# SMA_RF_CLK.net
KiCad netlist of a schematic drawn in Altium Designer
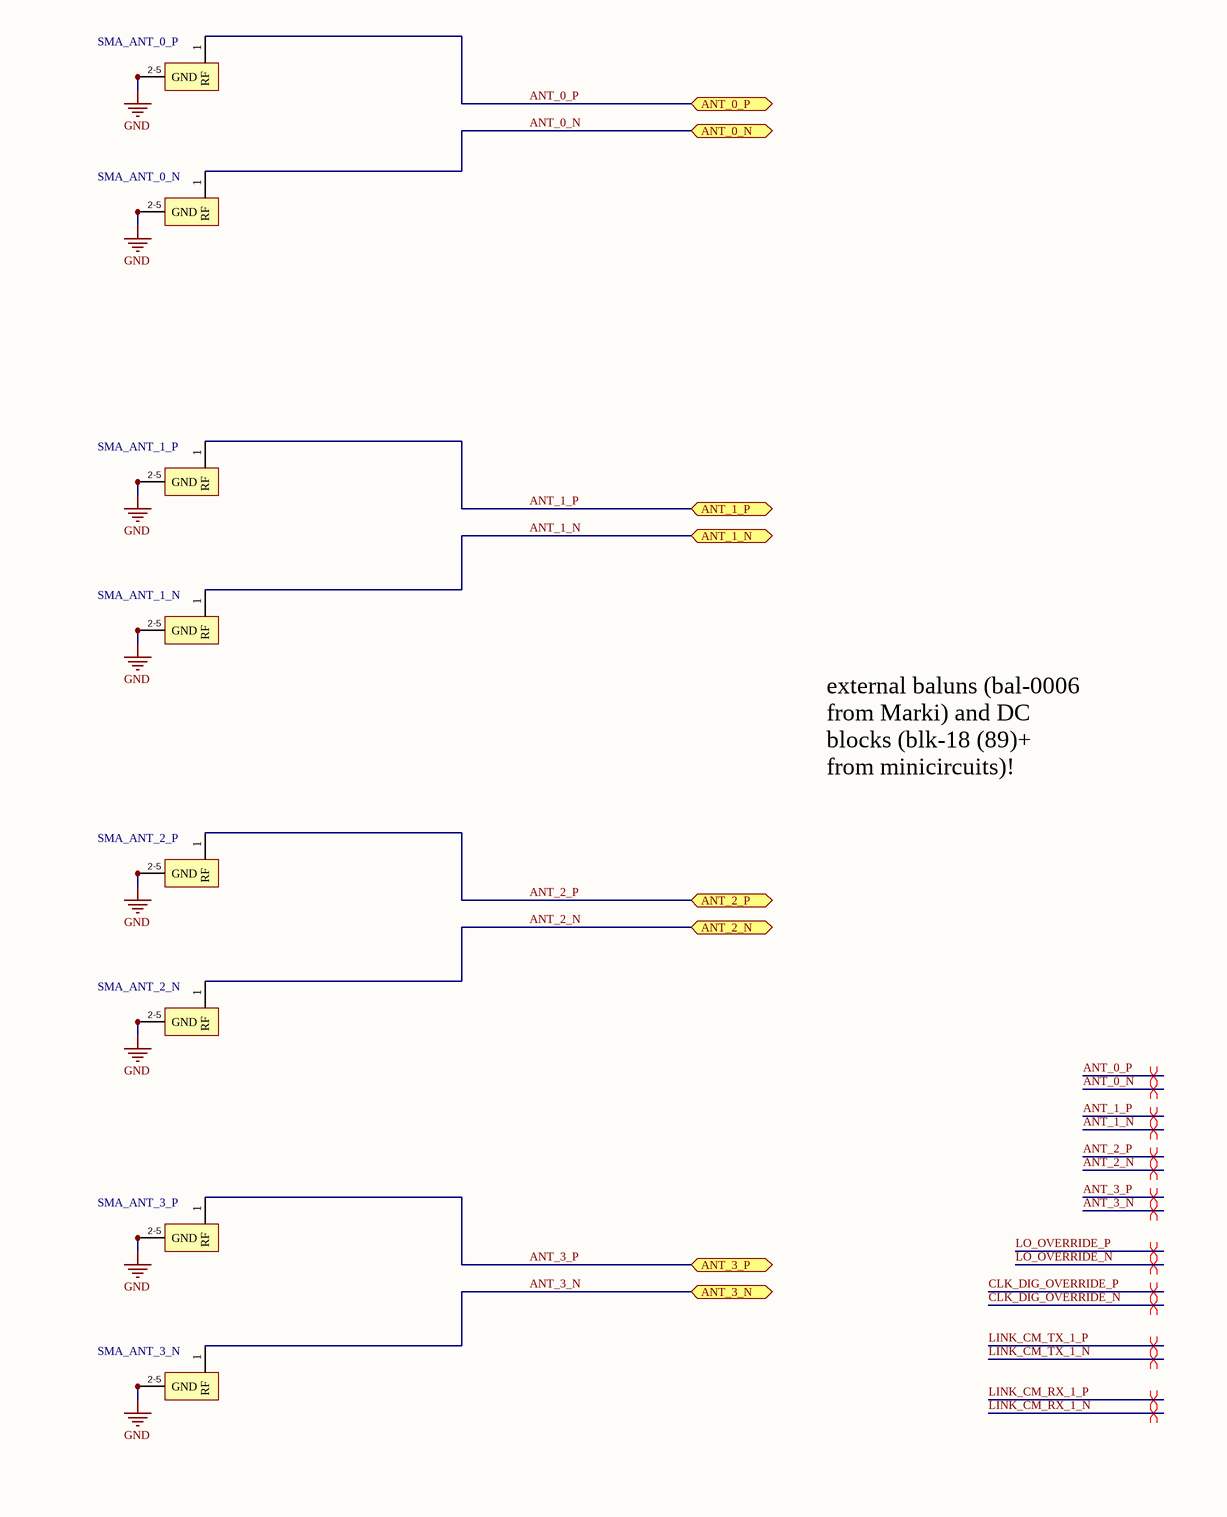
[diagram p0: SMA_RF_CLK.SchDoc, top]
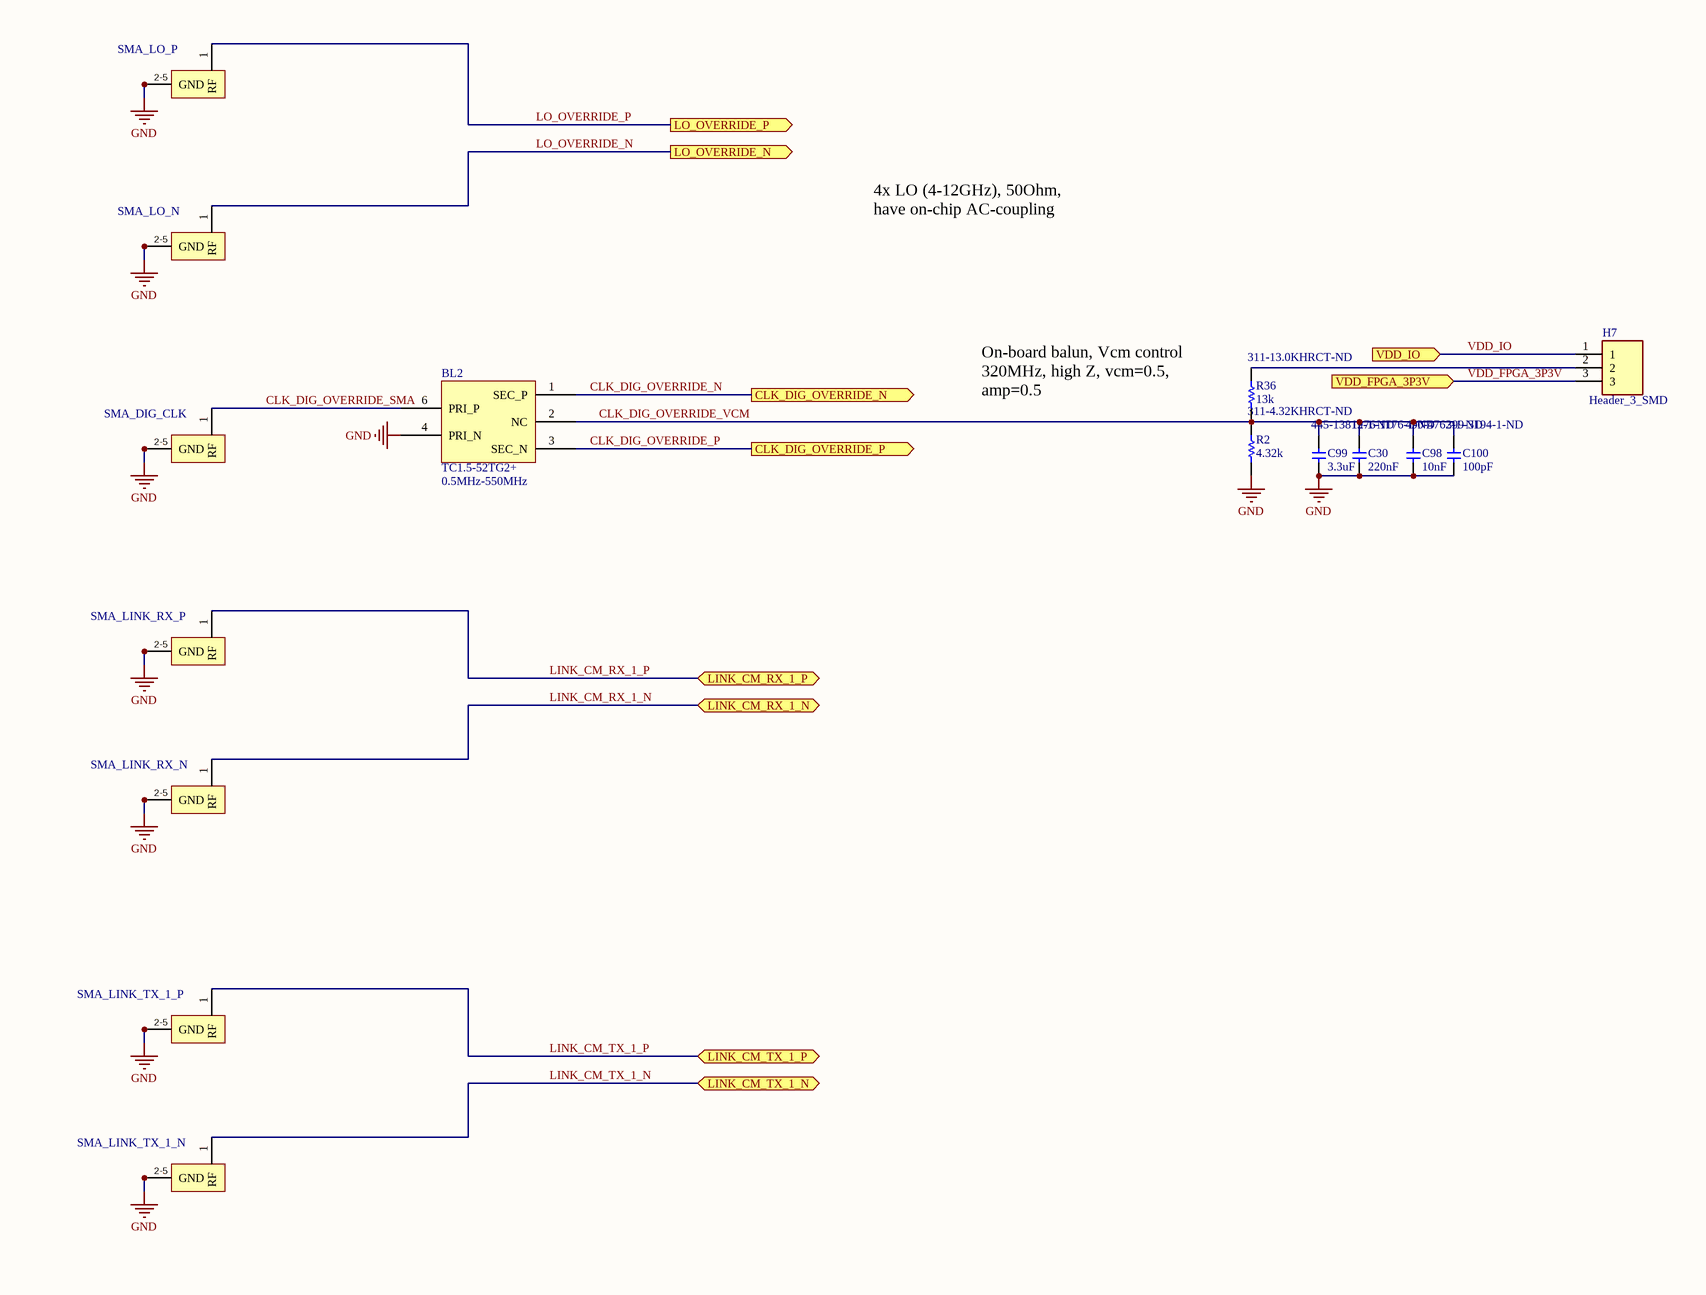
[diagram p1: SMA_RF_CLK.SchDoc, centre]
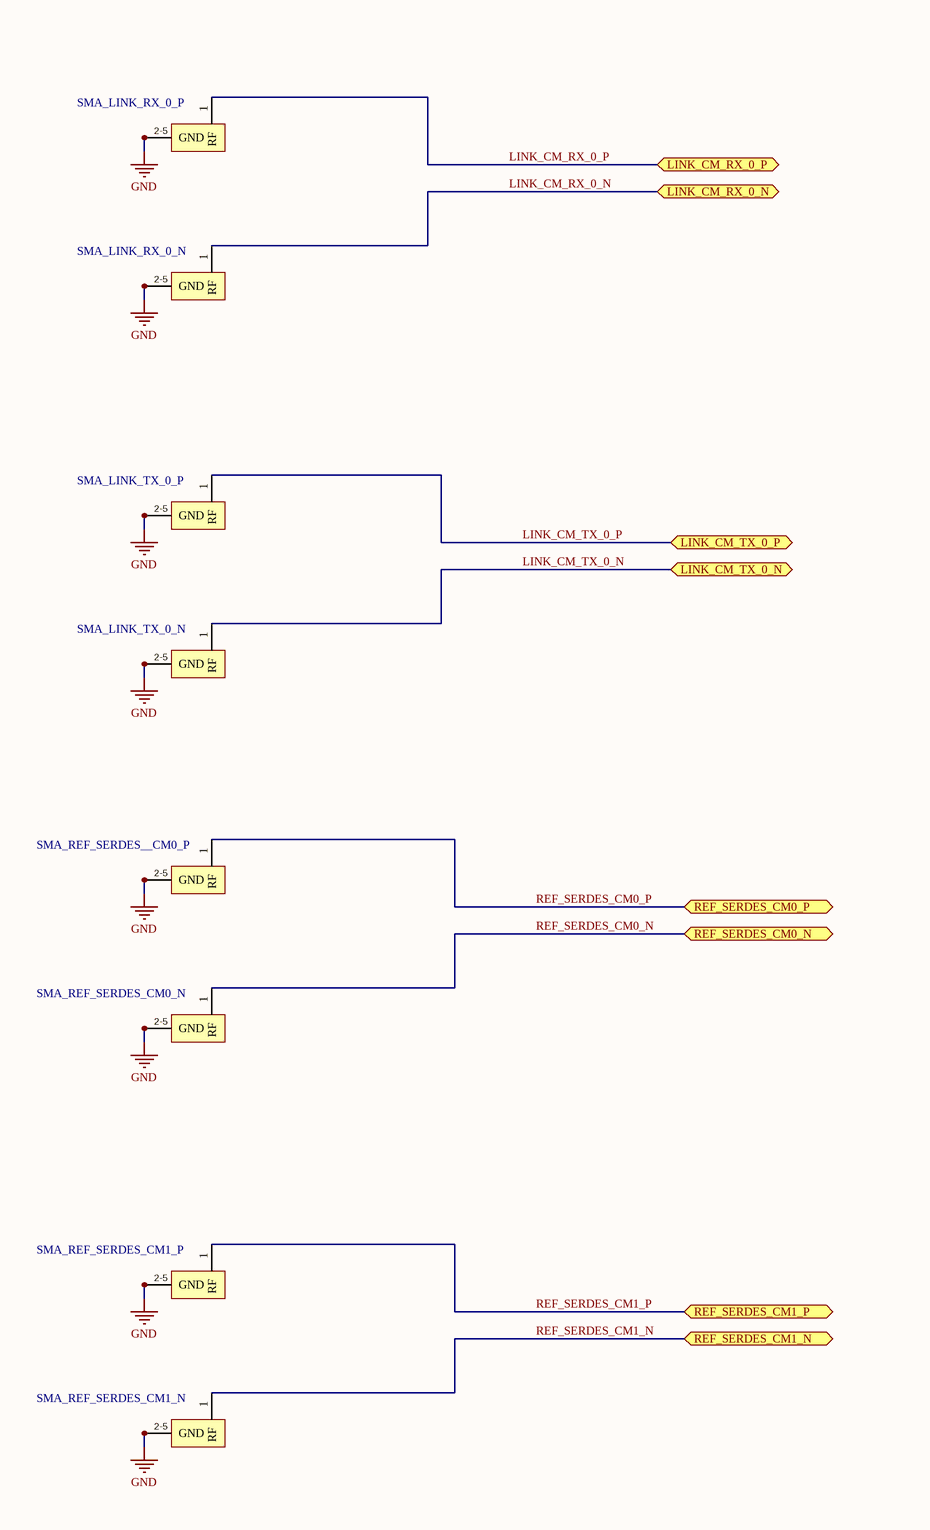
[diagram p2: SMA_RF_CLK.SchDoc, bottom]

(export (version "E")
  (design (tool "Eeschema 10.0.6"))
  (components
    (comp (ref "BL2")
      (value "TC1.5-52TG2+")
      (footprint "AT224-3")
      (description "Balun, 1:1.5 CORE & WIRE Transformer, 0.5 - 550 MHz, 50Ω")
      (fields (field (name "MANUFACTURER") "Mini-Circuits") (field (name "FREQUENCY RANGE") "0.5MHz-550MHz"))
      (libsource (lib "fader2_parts") (part "TC1.5-52TG2+"))
    )
    (comp (ref "C30")
      (value "220nF")
      (footprint "CAP_0402")
      (description "CAP CER 0.22uF 10% 16V X7R 0402")
      (fields
        (field (name "MANUFACTURER") "Samsung Electro-Mechanics")
        (field (name "SUPPLIER PART NUMBER 1") "1276-1176-1-ND")
      )
      (libsource (lib "fader2_parts") (part "cap 220nF"))
    )
    (comp (ref "C98")
      (value "10nF")
      (footprint "CAPC1005X06L_HD")
      (description "CAP CER 10nF 10% 50V X7R 0402")
      (fields (field (name "MANUFACTURER") "Murata") (field (name "SUPPLIER PART NUMBER 1") "490-4762-1-ND"))
      (libsource (lib "fader2_parts") (part "cap 10nF"))
    )
    (comp (ref "C99")
      (value "3.3uF")
      (footprint "CAP_0402")
      (description "CAP CER 3.3uF 10% 10V X5R 0402")
      (fields (field (name "MANUFACTURER") "TDK") (field (name "SUPPLIER PART NUMBER 1") "445-13819-1-ND"))
      (libsource (lib "fader2_parts") (part "cap 3p3uF"))
    )
    (comp (ref "C100")
      (value "100pF")
      (footprint "CAPC1005X06L_HD")
      (description "CAP CER 100pF 5% 50V C0G/NP0 0402")
      (fields (field (name "MANUFACTURER") "Kemet") (field (name "SUPPLIER PART NUMBER 1") "399-3194-1-ND"))
      (libsource (lib "fader2_parts") (part "cap 100pF 0402"))
    )
    (comp (ref "H7")
      (value "Header_3_SMD")
      (footprint "HDR1X3_SMD")
      (description "Connector Header Vertical, SMD, 3 position 0.100\" (2.54mm)")
      (fields
        (field (name "MANUFACTURER_PART_NUMBER") "TSM-103-01-S-SV-P-TR")
        (field (name "MOUSER PART NUMBER") "200-TSM10301SSVPTR")
      )
      (libsource (lib "fader2_parts") (part "Header_3_SMD"))
    )
    (comp (ref "R2")
      (value "4.32k")
      (footprint "RES_0603")
      (description "RES SMD 4.32kOHM 1% 1/10W 0603")
      (fields (field (name "SUPPLIER PART NUMBER 1") "311-4.32KHRCT-ND"))
      (libsource (lib "fader2_parts") (part "res 4.32 kOhm_1"))
    )
    (comp (ref "R36")
      (value "13k")
      (footprint "RES_0603")
      (description "RES SMD 13k OHM 1% 1/10W 0603")
      (fields (field (name "SUPPLIER PART NUMBER 1") "311-13.0KHRCT-ND"))
      (libsource (lib "fader2_parts") (part "res 13 kOhm_1"))
    )
    (comp (ref "SMA_ANT_0_N")
      (value "CONSMA001-SMD-G")
      (footprint "CON-SMA-SMD")
      (description "SMD SMA CONNECTOR")
      (libsource (lib "fader2_parts") (part "SURFACE MOUNT SMA CONNECTOR"))
    )
    (comp (ref "SMA_ANT_0_P")
      (value "CONSMA001-SMD-G")
      (footprint "CON-SMA-SMD")
      (description "SMD SMA CONNECTOR")
      (libsource (lib "fader2_parts") (part "SURFACE MOUNT SMA CONNECTOR"))
    )
    (comp (ref "SMA_ANT_1_N")
      (value "CONSMA001-SMD-G")
      (footprint "CON-SMA-SMD")
      (description "SMD SMA CONNECTOR")
      (libsource (lib "fader2_parts") (part "SURFACE MOUNT SMA CONNECTOR"))
    )
    (comp (ref "SMA_ANT_1_P")
      (value "CONSMA001-SMD-G")
      (footprint "CON-SMA-SMD")
      (description "SMD SMA CONNECTOR")
      (libsource (lib "fader2_parts") (part "SURFACE MOUNT SMA CONNECTOR"))
    )
    (comp (ref "SMA_ANT_2_N")
      (value "CONSMA001-SMD-G")
      (footprint "CON-SMA-SMD")
      (description "SMD SMA CONNECTOR")
      (libsource (lib "fader2_parts") (part "SURFACE MOUNT SMA CONNECTOR"))
    )
    (comp (ref "SMA_ANT_2_P")
      (value "CONSMA001-SMD-G")
      (footprint "CON-SMA-SMD")
      (description "SMD SMA CONNECTOR")
      (libsource (lib "fader2_parts") (part "SURFACE MOUNT SMA CONNECTOR"))
    )
    (comp (ref "SMA_ANT_3_N")
      (value "CONSMA001-SMD-G")
      (footprint "CON-SMA-SMD")
      (description "SMD SMA CONNECTOR")
      (libsource (lib "fader2_parts") (part "SURFACE MOUNT SMA CONNECTOR"))
    )
    (comp (ref "SMA_ANT_3_P")
      (value "CONSMA001-SMD-G")
      (footprint "CON-SMA-SMD")
      (description "SMD SMA CONNECTOR")
      (libsource (lib "fader2_parts") (part "SURFACE MOUNT SMA CONNECTOR"))
    )
    (comp (ref "SMA_DIG_CLK")
      (value "CONSMA001-SMD-G")
      (footprint "CON-SMA-SMD")
      (description "SMD SMA CONNECTOR")
      (libsource (lib "fader2_parts") (part "SURFACE MOUNT SMA CONNECTOR"))
    )
    (comp (ref "SMA_LINK_RX_0_N")
      (value "CONSMA001-SMD-G")
      (footprint "CON-SMA-SMD")
      (description "SMD SMA CONNECTOR")
      (libsource (lib "fader2_parts") (part "SURFACE MOUNT SMA CONNECTOR"))
    )
    (comp (ref "SMA_LINK_RX_0_P")
      (value "CONSMA001-SMD-G")
      (footprint "CON-SMA-SMD")
      (description "SMD SMA CONNECTOR")
      (libsource (lib "fader2_parts") (part "SURFACE MOUNT SMA CONNECTOR"))
    )
    (comp (ref "SMA_LINK_RX_N")
      (value "CONSMA001-SMD-G")
      (footprint "CON-SMA-SMD")
      (description "SMD SMA CONNECTOR")
      (libsource (lib "fader2_parts") (part "SURFACE MOUNT SMA CONNECTOR"))
    )
    (comp (ref "SMA_LINK_RX_P")
      (value "CONSMA001-SMD-G")
      (footprint "CON-SMA-SMD")
      (description "SMD SMA CONNECTOR")
      (libsource (lib "fader2_parts") (part "SURFACE MOUNT SMA CONNECTOR"))
    )
    (comp (ref "SMA_LINK_TX_0_N")
      (value "CONSMA001-SMD-G")
      (footprint "CON-SMA-SMD")
      (description "SMD SMA CONNECTOR")
      (libsource (lib "fader2_parts") (part "SURFACE MOUNT SMA CONNECTOR"))
    )
    (comp (ref "SMA_LINK_TX_0_P")
      (value "CONSMA001-SMD-G")
      (footprint "CON-SMA-SMD")
      (description "SMD SMA CONNECTOR")
      (libsource (lib "fader2_parts") (part "SURFACE MOUNT SMA CONNECTOR"))
    )
    (comp (ref "SMA_LINK_TX_1_N")
      (value "CONSMA001-SMD-G")
      (footprint "CON-SMA-SMD")
      (description "SMD SMA CONNECTOR")
      (libsource (lib "fader2_parts") (part "SURFACE MOUNT SMA CONNECTOR"))
    )
    (comp (ref "SMA_LINK_TX_1_P")
      (value "CONSMA001-SMD-G")
      (footprint "CON-SMA-SMD")
      (description "SMD SMA CONNECTOR")
      (libsource (lib "fader2_parts") (part "SURFACE MOUNT SMA CONNECTOR"))
    )
    (comp (ref "SMA_LO_N")
      (value "CONSMA001-SMD-G")
      (footprint "CON-SMA-SMD")
      (description "SMD SMA CONNECTOR")
      (libsource (lib "fader2_parts") (part "SURFACE MOUNT SMA CONNECTOR"))
    )
    (comp (ref "SMA_LO_P")
      (value "CONSMA001-SMD-G")
      (footprint "CON-SMA-SMD")
      (description "SMD SMA CONNECTOR")
      (libsource (lib "fader2_parts") (part "SURFACE MOUNT SMA CONNECTOR"))
    )
    (comp (ref "SMA_REF_SERDES_CM0_N")
      (value "CONSMA001-SMD-G")
      (footprint "CON-SMA-SMD")
      (description "SMD SMA CONNECTOR")
      (libsource (lib "fader2_parts") (part "SURFACE MOUNT SMA CONNECTOR"))
    )
    (comp (ref "SMA_REF_SERDES_CM1_N")
      (value "CONSMA001-SMD-G")
      (footprint "CON-SMA-SMD")
      (description "SMD SMA CONNECTOR")
      (libsource (lib "fader2_parts") (part "SURFACE MOUNT SMA CONNECTOR"))
    )
    (comp (ref "SMA_REF_SERDES_CM1_P")
      (value "CONSMA001-SMD-G")
      (footprint "CON-SMA-SMD")
      (description "SMD SMA CONNECTOR")
      (libsource (lib "fader2_parts") (part "SURFACE MOUNT SMA CONNECTOR"))
    )
    (comp (ref "SMA_REF_SERDES__CM0_P")
      (value "CONSMA001-SMD-G")
      (footprint "CON-SMA-SMD")
      (description "SMD SMA CONNECTOR")
      (libsource (lib "fader2_parts") (part "SURFACE MOUNT SMA CONNECTOR"))
    )
  )
  (nets
    (net (code "1") (name "/ANT_0_N") (class "Default")
      (node (ref "SMA_ANT_0_N") (pin "1") (pinfunction "RF_1") (pintype "passive"))
    )
    (net (code "2") (name "/ANT_0_P") (class "Default")
      (node (ref "SMA_ANT_0_P") (pin "1") (pinfunction "RF_1") (pintype "passive"))
    )
    (net (code "3") (name "/ANT_1_N") (class "Default")
      (node (ref "SMA_ANT_1_N") (pin "1") (pinfunction "RF_1") (pintype "passive"))
    )
    (net (code "4") (name "/ANT_1_P") (class "Default")
      (node (ref "SMA_ANT_1_P") (pin "1") (pinfunction "RF_1") (pintype "passive"))
    )
    (net (code "5") (name "/ANT_2_N") (class "Default")
      (node (ref "SMA_ANT_2_N") (pin "1") (pinfunction "RF_1") (pintype "passive"))
    )
    (net (code "6") (name "/ANT_2_P") (class "Default")
      (node (ref "SMA_ANT_2_P") (pin "1") (pinfunction "RF_1") (pintype "passive"))
    )
    (net (code "7") (name "/ANT_3_N") (class "Default")
      (node (ref "SMA_ANT_3_N") (pin "1") (pinfunction "RF_1") (pintype "passive"))
    )
    (net (code "8") (name "/ANT_3_P") (class "Default")
      (node (ref "SMA_ANT_3_P") (pin "1") (pinfunction "RF_1") (pintype "passive"))
    )
    (net (code "9") (name "/CLK_DIG_OVERRIDE_N") (class "Default")
      (node (ref "BL2") (pin "1") (pinfunction "SEC_P_1") (pintype "passive"))
    )
    (net (code "10") (name "/CLK_DIG_OVERRIDE_P") (class "Default")
      (node (ref "BL2") (pin "3") (pinfunction "SEC_N_3") (pintype "passive"))
    )
    (net (code "11") (name "/CLK_DIG_OVERRIDE_SMA") (class "Default")
      (node (ref "BL2") (pin "6") (pinfunction "PRI_P_6") (pintype "passive"))
      (node (ref "SMA_DIG_CLK") (pin "1") (pinfunction "RF_1") (pintype "passive"))
    )
    (net (code "12") (name "/CLK_DIG_OVERRIDE_VCM") (class "Default")
      (node (ref "BL2") (pin "2") (pinfunction "NC_2") (pintype "passive"))
      (node (ref "C100") (pin "1") (pinfunction "1_1") (pintype "passive"))
      (node (ref "C30") (pin "1") (pinfunction "1_1") (pintype "passive"))
      (node (ref "C98") (pin "1") (pinfunction "1_1") (pintype "passive"))
      (node (ref "C99") (pin "1") (pinfunction "1_1") (pintype "passive"))
      (node (ref "R2") (pin "1") (pinfunction "TOP_1") (pintype "passive"))
      (node (ref "R36") (pin "2") (pinfunction "BOT_2") (pintype "passive"))
    )
    (net (code "13") (name "/LINK_CM_RX_0_N") (class "Default")
      (node (ref "SMA_LINK_RX_0_N") (pin "1") (pinfunction "RF_1") (pintype "passive"))
    )
    (net (code "14") (name "/LINK_CM_RX_0_P") (class "Default")
      (node (ref "SMA_LINK_RX_0_P") (pin "1") (pinfunction "RF_1") (pintype "passive"))
    )
    (net (code "15") (name "/LINK_CM_RX_1_N") (class "Default")
      (node (ref "SMA_LINK_RX_N") (pin "1") (pinfunction "RF_1") (pintype "passive"))
    )
    (net (code "16") (name "/LINK_CM_RX_1_P") (class "Default")
      (node (ref "SMA_LINK_RX_P") (pin "1") (pinfunction "RF_1") (pintype "passive"))
    )
    (net (code "17") (name "/LINK_CM_TX_0_N") (class "Default")
      (node (ref "SMA_LINK_TX_0_N") (pin "1") (pinfunction "RF_1") (pintype "passive"))
    )
    (net (code "18") (name "/LINK_CM_TX_0_P") (class "Default")
      (node (ref "SMA_LINK_TX_0_P") (pin "1") (pinfunction "RF_1") (pintype "passive"))
    )
    (net (code "19") (name "/LINK_CM_TX_1_N") (class "Default")
      (node (ref "SMA_LINK_TX_1_N") (pin "1") (pinfunction "RF_1") (pintype "passive"))
    )
    (net (code "20") (name "/LINK_CM_TX_1_P") (class "Default")
      (node (ref "SMA_LINK_TX_1_P") (pin "1") (pinfunction "RF_1") (pintype "passive"))
    )
    (net (code "21") (name "/LO_OVERRIDE_N") (class "Default")
      (node (ref "SMA_LO_N") (pin "1") (pinfunction "RF_1") (pintype "passive"))
    )
    (net (code "22") (name "/LO_OVERRIDE_P") (class "Default")
      (node (ref "SMA_LO_P") (pin "1") (pinfunction "RF_1") (pintype "passive"))
    )
    (net (code "23") (name "/REF_SERDES_CM0_N") (class "Default")
      (node (ref "SMA_REF_SERDES_CM0_N") (pin "1") (pinfunction "RF_1") (pintype "passive"))
    )
    (net (code "24") (name "/REF_SERDES_CM0_P") (class "Default")
      (node (ref "SMA_REF_SERDES__CM0_P") (pin "1") (pinfunction "RF_1") (pintype "passive"))
    )
    (net (code "25") (name "/REF_SERDES_CM1_N") (class "Default")
      (node (ref "SMA_REF_SERDES_CM1_N") (pin "1") (pinfunction "RF_1") (pintype "passive"))
    )
    (net (code "26") (name "/REF_SERDES_CM1_P") (class "Default")
      (node (ref "SMA_REF_SERDES_CM1_P") (pin "1") (pinfunction "RF_1") (pintype "passive"))
    )
    (net (code "27") (name "/VDD_FPGA_3P3V") (class "Default")
      (node (ref "H7") (pin "3") (pinfunction "3_3") (pintype "passive"))
    )
    (net (code "28") (name "/VDD_IO") (class "Default")
      (node (ref "H7") (pin "1") (pinfunction "1_1") (pintype "passive"))
    )
    (net (code "29") (name "GND") (class "Default")
      (node (ref "BL2") (pin "4") (pinfunction "PRI_N_4") (pintype "passive"))
      (node (ref "C100") (pin "2") (pinfunction "2_2") (pintype "passive"))
      (node (ref "C30") (pin "2") (pinfunction "2_2") (pintype "passive"))
      (node (ref "C98") (pin "2") (pinfunction "2_2") (pintype "passive"))
      (node (ref "C99") (pin "2") (pinfunction "2_2") (pintype "passive"))
      (node (ref "R2") (pin "2") (pinfunction "BOT_2") (pintype "passive"))
      (node (ref "SMA_ANT_0_N") (pin "2") (pinfunction "GND_2") (pintype "passive"))
      (node (ref "SMA_ANT_0_N") (pin "3") (pinfunction "GND_3") (pintype "passive"))
      (node (ref "SMA_ANT_0_N") (pin "4") (pinfunction "GND_4") (pintype "passive"))
      (node (ref "SMA_ANT_0_N") (pin "5") (pinfunction "GND_5") (pintype "passive"))
      (node (ref "SMA_ANT_0_P") (pin "2") (pinfunction "GND_2") (pintype "passive"))
      (node (ref "SMA_ANT_0_P") (pin "3") (pinfunction "GND_3") (pintype "passive"))
      (node (ref "SMA_ANT_0_P") (pin "4") (pinfunction "GND_4") (pintype "passive"))
      (node (ref "SMA_ANT_0_P") (pin "5") (pinfunction "GND_5") (pintype "passive"))
      (node (ref "SMA_ANT_1_N") (pin "2") (pinfunction "GND_2") (pintype "passive"))
      (node (ref "SMA_ANT_1_N") (pin "3") (pinfunction "GND_3") (pintype "passive"))
      (node (ref "SMA_ANT_1_N") (pin "4") (pinfunction "GND_4") (pintype "passive"))
      (node (ref "SMA_ANT_1_N") (pin "5") (pinfunction "GND_5") (pintype "passive"))
      (node (ref "SMA_ANT_1_P") (pin "2") (pinfunction "GND_2") (pintype "passive"))
      (node (ref "SMA_ANT_1_P") (pin "3") (pinfunction "GND_3") (pintype "passive"))
      (node (ref "SMA_ANT_1_P") (pin "4") (pinfunction "GND_4") (pintype "passive"))
      (node (ref "SMA_ANT_1_P") (pin "5") (pinfunction "GND_5") (pintype "passive"))
      (node (ref "SMA_ANT_2_N") (pin "2") (pinfunction "GND_2") (pintype "passive"))
      (node (ref "SMA_ANT_2_N") (pin "3") (pinfunction "GND_3") (pintype "passive"))
      (node (ref "SMA_ANT_2_N") (pin "4") (pinfunction "GND_4") (pintype "passive"))
      (node (ref "SMA_ANT_2_N") (pin "5") (pinfunction "GND_5") (pintype "passive"))
      (node (ref "SMA_ANT_2_P") (pin "2") (pinfunction "GND_2") (pintype "passive"))
      (node (ref "SMA_ANT_2_P") (pin "3") (pinfunction "GND_3") (pintype "passive"))
      (node (ref "SMA_ANT_2_P") (pin "4") (pinfunction "GND_4") (pintype "passive"))
      (node (ref "SMA_ANT_2_P") (pin "5") (pinfunction "GND_5") (pintype "passive"))
      (node (ref "SMA_ANT_3_N") (pin "2") (pinfunction "GND_2") (pintype "passive"))
      (node (ref "SMA_ANT_3_N") (pin "3") (pinfunction "GND_3") (pintype "passive"))
      (node (ref "SMA_ANT_3_N") (pin "4") (pinfunction "GND_4") (pintype "passive"))
      (node (ref "SMA_ANT_3_N") (pin "5") (pinfunction "GND_5") (pintype "passive"))
      (node (ref "SMA_ANT_3_P") (pin "2") (pinfunction "GND_2") (pintype "passive"))
      (node (ref "SMA_ANT_3_P") (pin "3") (pinfunction "GND_3") (pintype "passive"))
      (node (ref "SMA_ANT_3_P") (pin "4") (pinfunction "GND_4") (pintype "passive"))
      (node (ref "SMA_ANT_3_P") (pin "5") (pinfunction "GND_5") (pintype "passive"))
      (node (ref "SMA_DIG_CLK") (pin "2") (pinfunction "GND_2") (pintype "passive"))
      (node (ref "SMA_DIG_CLK") (pin "3") (pinfunction "GND_3") (pintype "passive"))
      (node (ref "SMA_DIG_CLK") (pin "4") (pinfunction "GND_4") (pintype "passive"))
      (node (ref "SMA_DIG_CLK") (pin "5") (pinfunction "GND_5") (pintype "passive"))
      (node (ref "SMA_LINK_RX_0_N") (pin "2") (pinfunction "GND_2") (pintype "passive"))
      (node (ref "SMA_LINK_RX_0_N") (pin "3") (pinfunction "GND_3") (pintype "passive"))
      (node (ref "SMA_LINK_RX_0_N") (pin "4") (pinfunction "GND_4") (pintype "passive"))
      (node (ref "SMA_LINK_RX_0_N") (pin "5") (pinfunction "GND_5") (pintype "passive"))
      (node (ref "SMA_LINK_RX_0_P") (pin "2") (pinfunction "GND_2") (pintype "passive"))
      (node (ref "SMA_LINK_RX_0_P") (pin "3") (pinfunction "GND_3") (pintype "passive"))
      (node (ref "SMA_LINK_RX_0_P") (pin "4") (pinfunction "GND_4") (pintype "passive"))
      (node (ref "SMA_LINK_RX_0_P") (pin "5") (pinfunction "GND_5") (pintype "passive"))
      (node (ref "SMA_LINK_RX_N") (pin "2") (pinfunction "GND_2") (pintype "passive"))
      (node (ref "SMA_LINK_RX_N") (pin "3") (pinfunction "GND_3") (pintype "passive"))
      (node (ref "SMA_LINK_RX_N") (pin "4") (pinfunction "GND_4") (pintype "passive"))
      (node (ref "SMA_LINK_RX_N") (pin "5") (pinfunction "GND_5") (pintype "passive"))
      (node (ref "SMA_LINK_RX_P") (pin "2") (pinfunction "GND_2") (pintype "passive"))
      (node (ref "SMA_LINK_RX_P") (pin "3") (pinfunction "GND_3") (pintype "passive"))
      (node (ref "SMA_LINK_RX_P") (pin "4") (pinfunction "GND_4") (pintype "passive"))
      (node (ref "SMA_LINK_RX_P") (pin "5") (pinfunction "GND_5") (pintype "passive"))
      (node (ref "SMA_LINK_TX_0_N") (pin "2") (pinfunction "GND_2") (pintype "passive"))
      (node (ref "SMA_LINK_TX_0_N") (pin "3") (pinfunction "GND_3") (pintype "passive"))
      (node (ref "SMA_LINK_TX_0_N") (pin "4") (pinfunction "GND_4") (pintype "passive"))
      (node (ref "SMA_LINK_TX_0_N") (pin "5") (pinfunction "GND_5") (pintype "passive"))
      (node (ref "SMA_LINK_TX_0_P") (pin "2") (pinfunction "GND_2") (pintype "passive"))
      (node (ref "SMA_LINK_TX_0_P") (pin "3") (pinfunction "GND_3") (pintype "passive"))
      (node (ref "SMA_LINK_TX_0_P") (pin "4") (pinfunction "GND_4") (pintype "passive"))
      (node (ref "SMA_LINK_TX_0_P") (pin "5") (pinfunction "GND_5") (pintype "passive"))
      (node (ref "SMA_LINK_TX_1_N") (pin "2") (pinfunction "GND_2") (pintype "passive"))
      (node (ref "SMA_LINK_TX_1_N") (pin "3") (pinfunction "GND_3") (pintype "passive"))
      (node (ref "SMA_LINK_TX_1_N") (pin "4") (pinfunction "GND_4") (pintype "passive"))
      (node (ref "SMA_LINK_TX_1_N") (pin "5") (pinfunction "GND_5") (pintype "passive"))
      (node (ref "SMA_LINK_TX_1_P") (pin "2") (pinfunction "GND_2") (pintype "passive"))
      (node (ref "SMA_LINK_TX_1_P") (pin "3") (pinfunction "GND_3") (pintype "passive"))
      (node (ref "SMA_LINK_TX_1_P") (pin "4") (pinfunction "GND_4") (pintype "passive"))
      (node (ref "SMA_LINK_TX_1_P") (pin "5") (pinfunction "GND_5") (pintype "passive"))
      (node (ref "SMA_LO_N") (pin "2") (pinfunction "GND_2") (pintype "passive"))
      (node (ref "SMA_LO_N") (pin "3") (pinfunction "GND_3") (pintype "passive"))
      (node (ref "SMA_LO_N") (pin "4") (pinfunction "GND_4") (pintype "passive"))
      (node (ref "SMA_LO_N") (pin "5") (pinfunction "GND_5") (pintype "passive"))
      (node (ref "SMA_LO_P") (pin "2") (pinfunction "GND_2") (pintype "passive"))
      (node (ref "SMA_LO_P") (pin "3") (pinfunction "GND_3") (pintype "passive"))
      (node (ref "SMA_LO_P") (pin "4") (pinfunction "GND_4") (pintype "passive"))
      (node (ref "SMA_LO_P") (pin "5") (pinfunction "GND_5") (pintype "passive"))
      (node (ref "SMA_REF_SERDES_CM0_N") (pin "2") (pinfunction "GND_2") (pintype "passive"))
      (node (ref "SMA_REF_SERDES_CM0_N") (pin "3") (pinfunction "GND_3") (pintype "passive"))
      (node (ref "SMA_REF_SERDES_CM0_N") (pin "4") (pinfunction "GND_4") (pintype "passive"))
      (node (ref "SMA_REF_SERDES_CM0_N") (pin "5") (pinfunction "GND_5") (pintype "passive"))
      (node (ref "SMA_REF_SERDES_CM1_N") (pin "2") (pinfunction "GND_2") (pintype "passive"))
      (node (ref "SMA_REF_SERDES_CM1_N") (pin "3") (pinfunction "GND_3") (pintype "passive"))
      (node (ref "SMA_REF_SERDES_CM1_N") (pin "4") (pinfunction "GND_4") (pintype "passive"))
      (node (ref "SMA_REF_SERDES_CM1_N") (pin "5") (pinfunction "GND_5") (pintype "passive"))
      (node (ref "SMA_REF_SERDES_CM1_P") (pin "2") (pinfunction "GND_2") (pintype "passive"))
      (node (ref "SMA_REF_SERDES_CM1_P") (pin "3") (pinfunction "GND_3") (pintype "passive"))
      (node (ref "SMA_REF_SERDES_CM1_P") (pin "4") (pinfunction "GND_4") (pintype "passive"))
      (node (ref "SMA_REF_SERDES_CM1_P") (pin "5") (pinfunction "GND_5") (pintype "passive"))
      (node (ref "SMA_REF_SERDES__CM0_P") (pin "2") (pinfunction "GND_2") (pintype "passive"))
      (node (ref "SMA_REF_SERDES__CM0_P") (pin "3") (pinfunction "GND_3") (pintype "passive"))
      (node (ref "SMA_REF_SERDES__CM0_P") (pin "4") (pinfunction "GND_4") (pintype "passive"))
      (node (ref "SMA_REF_SERDES__CM0_P") (pin "5") (pinfunction "GND_5") (pintype "passive"))
    )
    (net (code "30") (name "Net-(R36-TOP)") (class "Default")
      (node (ref "H7") (pin "2") (pinfunction "2_2") (pintype "passive"))
      (node (ref "R36") (pin "1") (pinfunction "TOP_1") (pintype "passive"))
    )
  )
)
